# 12_Supply.net
KiCad netlist of a schematic drawn in Altium Designer
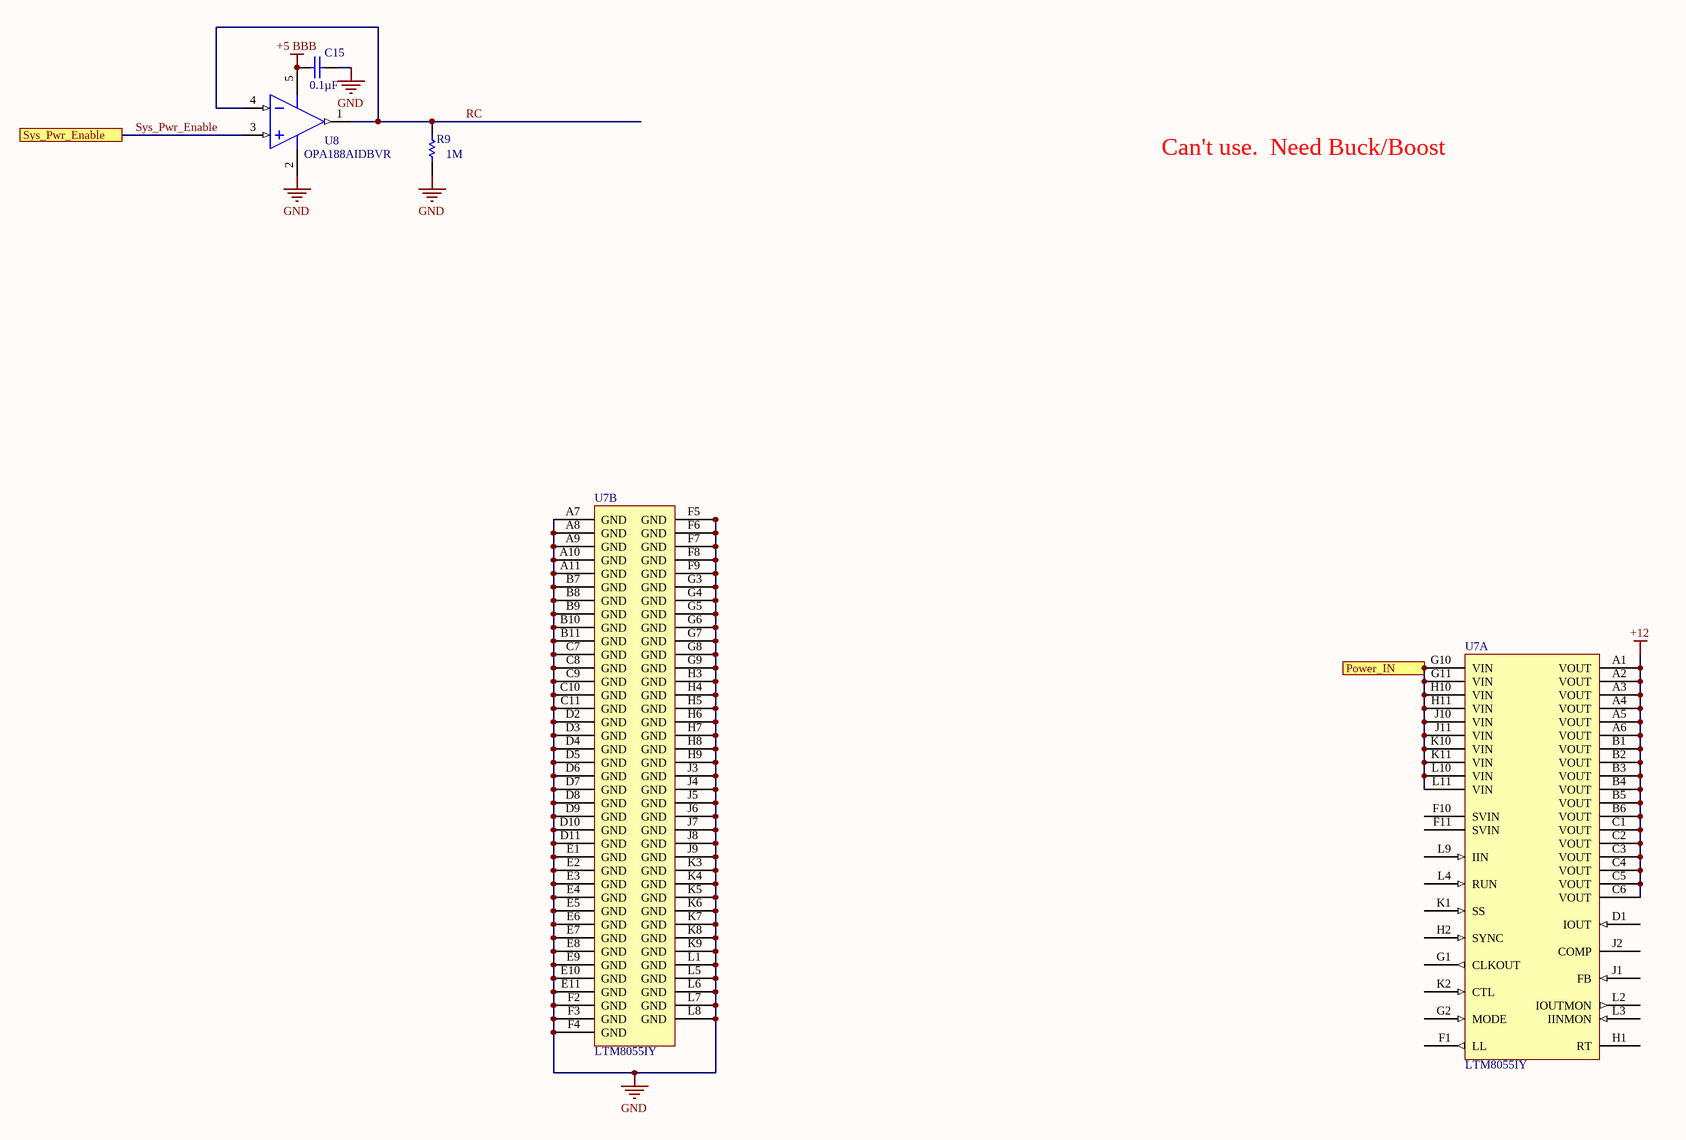
[diagram p0: 12_Supply.SchDoc]

(export (version "E")
  (design (tool "Eeschema 10.0.6"))
  (components
    (comp (ref "C15")
      (value "CAP CER 0.1UF 16V X7R 0805")
      (footprint "CAPC0805(2012)145_N")
      (fields
        (field (name "TOLERANCE") "±10%")
        (field (name "MANUFACTURER") "Murata Electronics North America")
        (field (name "MANUFACTURER PART NUMBER") "GRM219R71C104KA01D")
        (field (name "CAPACITANCE") "0.1µF")
      )
      (libsource (lib "Altium Content Vault") (part "CMP-1036-04795-1"))
    )
    (comp (ref "R9")
      (value "1M")
      (footprint "RESC0402(1005)_L")
      (fields (field (name "TOLERANCE") "±1%"))
      (libsource (lib "Altium Content Vault") (part "CMP-1011-00927-1"))
    )
    (comp (ref "U7")
      (value "LTM8055IY")
      (footprint "LT-BGA-121-15000X15000X4920")
      (description "Buck-Boost uModule Regulator, 8.5 A, 5 to 36 V, -40 to 125 degC, 121-Ball BGA, RoHS, Tray")
      (fields (field (name "MANUFACTURER") "LinearTechnology"))
      (libsource (lib "Altium Content Vault") (part "LT-LTM8055-BGA-121"))
    )
    (comp (ref "U8")
      (value "OPA188AIDBVR")
      (footprint "DBV0005A_M")
      (fields (field (name "MANUFACTURER") "Texas Instruments"))
      (libsource (lib "Altium Content Vault") (part "CMP-0809-00005-2"))
    )
  )
  (nets
    (net (code "1") (name "+5 BBB") (class "Default")
      (node (ref "C15") (pin "1") (pinfunction "1_1") (pintype "passive"))
      (node (ref "U8") (pin "5") (pinfunction "V+_5") (pintype "power_in"))
    )
    (net (code "2") (name "+12") (class "Default")
      (node (ref "U7") (pin "A1") (pinfunction "VOUT_A1") (pintype "power_in"))
      (node (ref "U7") (pin "A2") (pinfunction "VOUT_A2") (pintype "power_in"))
      (node (ref "U7") (pin "A3") (pinfunction "VOUT_A3") (pintype "power_in"))
      (node (ref "U7") (pin "A4") (pinfunction "VOUT_A4") (pintype "power_in"))
      (node (ref "U7") (pin "A5") (pinfunction "VOUT_A5") (pintype "power_in"))
      (node (ref "U7") (pin "A6") (pinfunction "VOUT_A6") (pintype "power_in"))
      (node (ref "U7") (pin "B1") (pinfunction "VOUT_B1") (pintype "power_in"))
      (node (ref "U7") (pin "B2") (pinfunction "VOUT_B2") (pintype "power_in"))
      (node (ref "U7") (pin "B3") (pinfunction "VOUT_B3") (pintype "power_in"))
      (node (ref "U7") (pin "B4") (pinfunction "VOUT_B4") (pintype "power_in"))
      (node (ref "U7") (pin "B5") (pinfunction "VOUT_B5") (pintype "power_in"))
      (node (ref "U7") (pin "B6") (pinfunction "VOUT_B6") (pintype "power_in"))
      (node (ref "U7") (pin "C1") (pinfunction "VOUT_C1") (pintype "power_in"))
      (node (ref "U7") (pin "C2") (pinfunction "VOUT_C2") (pintype "power_in"))
      (node (ref "U7") (pin "C3") (pinfunction "VOUT_C3") (pintype "power_in"))
      (node (ref "U7") (pin "C4") (pinfunction "VOUT_C4") (pintype "power_in"))
      (node (ref "U7") (pin "C5") (pinfunction "VOUT_C5") (pintype "power_in"))
      (node (ref "U7") (pin "C6") (pinfunction "VOUT_C6") (pintype "power_in"))
    )
    (net (code "3") (name "/Power_IN") (class "Default")
      (node (ref "U7") (pin "G10") (pinfunction "VIN_G10") (pintype "power_in"))
      (node (ref "U7") (pin "G11") (pinfunction "VIN_G11") (pintype "power_in"))
      (node (ref "U7") (pin "H10") (pinfunction "VIN_H10") (pintype "power_in"))
      (node (ref "U7") (pin "H11") (pinfunction "VIN_H11") (pintype "power_in"))
      (node (ref "U7") (pin "J10") (pinfunction "VIN_J10") (pintype "power_in"))
      (node (ref "U7") (pin "J11") (pinfunction "VIN_J11") (pintype "power_in"))
      (node (ref "U7") (pin "K10") (pinfunction "VIN_K10") (pintype "power_in"))
      (node (ref "U7") (pin "K11") (pinfunction "VIN_K11") (pintype "power_in"))
      (node (ref "U7") (pin "L10") (pinfunction "VIN_L10") (pintype "power_in"))
      (node (ref "U7") (pin "L11") (pinfunction "VIN_L11") (pintype "power_in"))
    )
    (net (code "4") (name "/RC") (class "Default")
      (node (ref "R9") (pin "2") (pinfunction "2_2") (pintype "passive"))
      (node (ref "U8") (pin "1") (pinfunction "OUT_1") (pintype "output"))
      (node (ref "U8") (pin "4") (pinfunction "IN-_4") (pintype "input"))
    )
    (net (code "5") (name "/Sys_Pwr_Enable") (class "Default")
      (node (ref "U8") (pin "3") (pinfunction "IN+_3") (pintype "input"))
    )
    (net (code "6") (name "GND") (class "Default")
      (node (ref "C15") (pin "2") (pinfunction "2_2") (pintype "passive"))
      (node (ref "R9") (pin "1") (pinfunction "1_1") (pintype "passive"))
      (node (ref "U7") (pin "A10") (pinfunction "GND_A10") (pintype "power_in"))
      (node (ref "U7") (pin "A11") (pinfunction "GND_A11") (pintype "power_in"))
      (node (ref "U7") (pin "A7") (pinfunction "GND_A7") (pintype "power_in"))
      (node (ref "U7") (pin "A8") (pinfunction "GND_A8") (pintype "power_in"))
      (node (ref "U7") (pin "A9") (pinfunction "GND_A9") (pintype "power_in"))
      (node (ref "U7") (pin "B10") (pinfunction "GND_B10") (pintype "power_in"))
      (node (ref "U7") (pin "B11") (pinfunction "GND_B11") (pintype "power_in"))
      (node (ref "U7") (pin "B7") (pinfunction "GND_B7") (pintype "power_in"))
      (node (ref "U7") (pin "B8") (pinfunction "GND_B8") (pintype "power_in"))
      (node (ref "U7") (pin "B9") (pinfunction "GND_B9") (pintype "power_in"))
      (node (ref "U7") (pin "C10") (pinfunction "GND_C10") (pintype "power_in"))
      (node (ref "U7") (pin "C11") (pinfunction "GND_C11") (pintype "power_in"))
      (node (ref "U7") (pin "C7") (pinfunction "GND_C7") (pintype "power_in"))
      (node (ref "U7") (pin "C8") (pinfunction "GND_C8") (pintype "power_in"))
      (node (ref "U7") (pin "C9") (pinfunction "GND_C9") (pintype "power_in"))
      (node (ref "U7") (pin "D10") (pinfunction "GND_D10") (pintype "power_in"))
      (node (ref "U7") (pin "D11") (pinfunction "GND_D11") (pintype "power_in"))
      (node (ref "U7") (pin "D2") (pinfunction "GND_D2") (pintype "power_in"))
      (node (ref "U7") (pin "D3") (pinfunction "GND_D3") (pintype "power_in"))
      (node (ref "U7") (pin "D4") (pinfunction "GND_D4") (pintype "power_in"))
      (node (ref "U7") (pin "D5") (pinfunction "GND_D5") (pintype "power_in"))
      (node (ref "U7") (pin "D6") (pinfunction "GND_D6") (pintype "power_in"))
      (node (ref "U7") (pin "D7") (pinfunction "GND_D7") (pintype "power_in"))
      (node (ref "U7") (pin "D8") (pinfunction "GND_D8") (pintype "power_in"))
      (node (ref "U7") (pin "D9") (pinfunction "GND_D9") (pintype "power_in"))
      (node (ref "U7") (pin "E1") (pinfunction "GND_E1") (pintype "power_in"))
      (node (ref "U7") (pin "E10") (pinfunction "GND_E10") (pintype "power_in"))
      (node (ref "U7") (pin "E11") (pinfunction "GND_E11") (pintype "power_in"))
      (node (ref "U7") (pin "E2") (pinfunction "GND_E2") (pintype "power_in"))
      (node (ref "U7") (pin "E3") (pinfunction "GND_E3") (pintype "power_in"))
      (node (ref "U7") (pin "E4") (pinfunction "GND_E4") (pintype "power_in"))
      (node (ref "U7") (pin "E5") (pinfunction "GND_E5") (pintype "power_in"))
      (node (ref "U7") (pin "E6") (pinfunction "GND_E6") (pintype "power_in"))
      (node (ref "U7") (pin "E7") (pinfunction "GND_E7") (pintype "power_in"))
      (node (ref "U7") (pin "E8") (pinfunction "GND_E8") (pintype "power_in"))
      (node (ref "U7") (pin "E9") (pinfunction "GND_E9") (pintype "power_in"))
      (node (ref "U7") (pin "F2") (pinfunction "GND_F2") (pintype "power_in"))
      (node (ref "U7") (pin "F3") (pinfunction "GND_F3") (pintype "power_in"))
      (node (ref "U7") (pin "F4") (pinfunction "GND_F4") (pintype "power_in"))
      (node (ref "U7") (pin "F5") (pinfunction "GND_F5") (pintype "power_in"))
      (node (ref "U7") (pin "F6") (pinfunction "GND_F6") (pintype "power_in"))
      (node (ref "U7") (pin "F7") (pinfunction "GND_F7") (pintype "power_in"))
      (node (ref "U7") (pin "F8") (pinfunction "GND_F8") (pintype "power_in"))
      (node (ref "U7") (pin "F9") (pinfunction "GND_F9") (pintype "power_in"))
      (node (ref "U7") (pin "G3") (pinfunction "GND_G3") (pintype "power_in"))
      (node (ref "U7") (pin "G4") (pinfunction "GND_G4") (pintype "power_in"))
      (node (ref "U7") (pin "G5") (pinfunction "GND_G5") (pintype "power_in"))
      (node (ref "U7") (pin "G6") (pinfunction "GND_G6") (pintype "power_in"))
      (node (ref "U7") (pin "G7") (pinfunction "GND_G7") (pintype "power_in"))
      (node (ref "U7") (pin "G8") (pinfunction "GND_G8") (pintype "power_in"))
      (node (ref "U7") (pin "G9") (pinfunction "GND_G9") (pintype "power_in"))
      (node (ref "U7") (pin "H3") (pinfunction "GND_H3") (pintype "power_in"))
      (node (ref "U7") (pin "H4") (pinfunction "GND_H4") (pintype "power_in"))
      (node (ref "U7") (pin "H5") (pinfunction "GND_H5") (pintype "power_in"))
      (node (ref "U7") (pin "H6") (pinfunction "GND_H6") (pintype "power_in"))
      (node (ref "U7") (pin "H7") (pinfunction "GND_H7") (pintype "power_in"))
      (node (ref "U7") (pin "H8") (pinfunction "GND_H8") (pintype "power_in"))
      (node (ref "U7") (pin "H9") (pinfunction "GND_H9") (pintype "power_in"))
      (node (ref "U7") (pin "J3") (pinfunction "GND_J3") (pintype "power_in"))
      (node (ref "U7") (pin "J4") (pinfunction "GND_J4") (pintype "power_in"))
      (node (ref "U7") (pin "J5") (pinfunction "GND_J5") (pintype "power_in"))
      (node (ref "U7") (pin "J6") (pinfunction "GND_J6") (pintype "power_in"))
      (node (ref "U7") (pin "J7") (pinfunction "GND_J7") (pintype "power_in"))
      (node (ref "U7") (pin "J8") (pinfunction "GND_J8") (pintype "power_in"))
      (node (ref "U7") (pin "J9") (pinfunction "GND_J9") (pintype "power_in"))
      (node (ref "U7") (pin "K3") (pinfunction "GND_K3") (pintype "power_in"))
      (node (ref "U7") (pin "K4") (pinfunction "GND_K4") (pintype "power_in"))
      (node (ref "U7") (pin "K5") (pinfunction "GND_K5") (pintype "power_in"))
      (node (ref "U7") (pin "K6") (pinfunction "GND_K6") (pintype "power_in"))
      (node (ref "U7") (pin "K7") (pinfunction "GND_K7") (pintype "power_in"))
      (node (ref "U7") (pin "K8") (pinfunction "GND_K8") (pintype "power_in"))
      (node (ref "U7") (pin "K9") (pinfunction "GND_K9") (pintype "power_in"))
      (node (ref "U7") (pin "L1") (pinfunction "GND_L1") (pintype "power_in"))
      (node (ref "U7") (pin "L5") (pinfunction "GND_L5") (pintype "power_in"))
      (node (ref "U7") (pin "L6") (pinfunction "GND_L6") (pintype "power_in"))
      (node (ref "U7") (pin "L7") (pinfunction "GND_L7") (pintype "power_in"))
      (node (ref "U7") (pin "L8") (pinfunction "GND_L8") (pintype "power_in"))
      (node (ref "U8") (pin "2") (pinfunction "V-_2") (pintype "power_in"))
    )
    (net (code "7") (name "unconnected-(U7A-CLKOUT-PadG1)") (class "Default")
      (node (ref "U7") (pin "G1") (pinfunction "CLKOUT_G1") (pintype "output"))
    )
    (net (code "8") (name "unconnected-(U7A-COMP-PadJ2)") (class "Default")
      (node (ref "U7") (pin "J2") (pinfunction "COMP_J2") (pintype "passive"))
    )
    (net (code "9") (name "unconnected-(U7A-CTL-PadK2)") (class "Default")
      (node (ref "U7") (pin "K2") (pinfunction "CTL_K2") (pintype "input"))
    )
    (net (code "10") (name "unconnected-(U7A-FB-PadJ1)") (class "Default")
      (node (ref "U7") (pin "J1") (pinfunction "FB_J1") (pintype "input"))
    )
    (net (code "11") (name "unconnected-(U7A-IIN-PadL9)") (class "Default")
      (node (ref "U7") (pin "L9") (pinfunction "IIN_L9") (pintype "input"))
    )
    (net (code "12") (name "unconnected-(U7A-IINMON-PadL3)") (class "Default")
      (node (ref "U7") (pin "L3") (pinfunction "IINMON_L3") (pintype "input"))
    )
    (net (code "13") (name "unconnected-(U7A-IOUT-PadD1)") (class "Default")
      (node (ref "U7") (pin "D1") (pinfunction "IOUT_D1") (pintype "input"))
    )
    (net (code "14") (name "unconnected-(U7A-IOUTMON-PadL2)") (class "Default")
      (node (ref "U7") (pin "L2") (pinfunction "IOUTMON_L2") (pintype "output"))
    )
    (net (code "15") (name "unconnected-(U7A-LL-PadF1)") (class "Default")
      (node (ref "U7") (pin "F1") (pinfunction "LL_F1") (pintype "output"))
    )
    (net (code "16") (name "unconnected-(U7A-MODE-PadG2)") (class "Default")
      (node (ref "U7") (pin "G2") (pinfunction "MODE_G2") (pintype "input"))
    )
    (net (code "17") (name "unconnected-(U7A-RT-PadH1)") (class "Default")
      (node (ref "U7") (pin "H1") (pinfunction "RT_H1") (pintype "passive"))
    )
    (net (code "18") (name "unconnected-(U7A-RUN-PadL4)") (class "Default")
      (node (ref "U7") (pin "L4") (pinfunction "RUN_L4") (pintype "input"))
    )
    (net (code "19") (name "unconnected-(U7A-SS-PadK1)") (class "Default")
      (node (ref "U7") (pin "K1") (pinfunction "SS_K1") (pintype "input"))
    )
    (net (code "20") (name "unconnected-(U7A-SVIN-PadF10)") (class "Default")
      (node (ref "U7") (pin "F10") (pinfunction "SVIN_F10") (pintype "power_in"))
    )
    (net (code "21") (name "unconnected-(U7A-SVIN-PadF11)") (class "Default")
      (node (ref "U7") (pin "F11") (pinfunction "SVIN_F11") (pintype "power_in"))
    )
    (net (code "22") (name "unconnected-(U7A-SYNC-PadH2)") (class "Default")
      (node (ref "U7") (pin "H2") (pinfunction "SYNC_H2") (pintype "input"))
    )
  )
)
